# krajBB-Moj_i__MatejFIN2.net
KiCad netlist of a schematic drawn in EAGLE
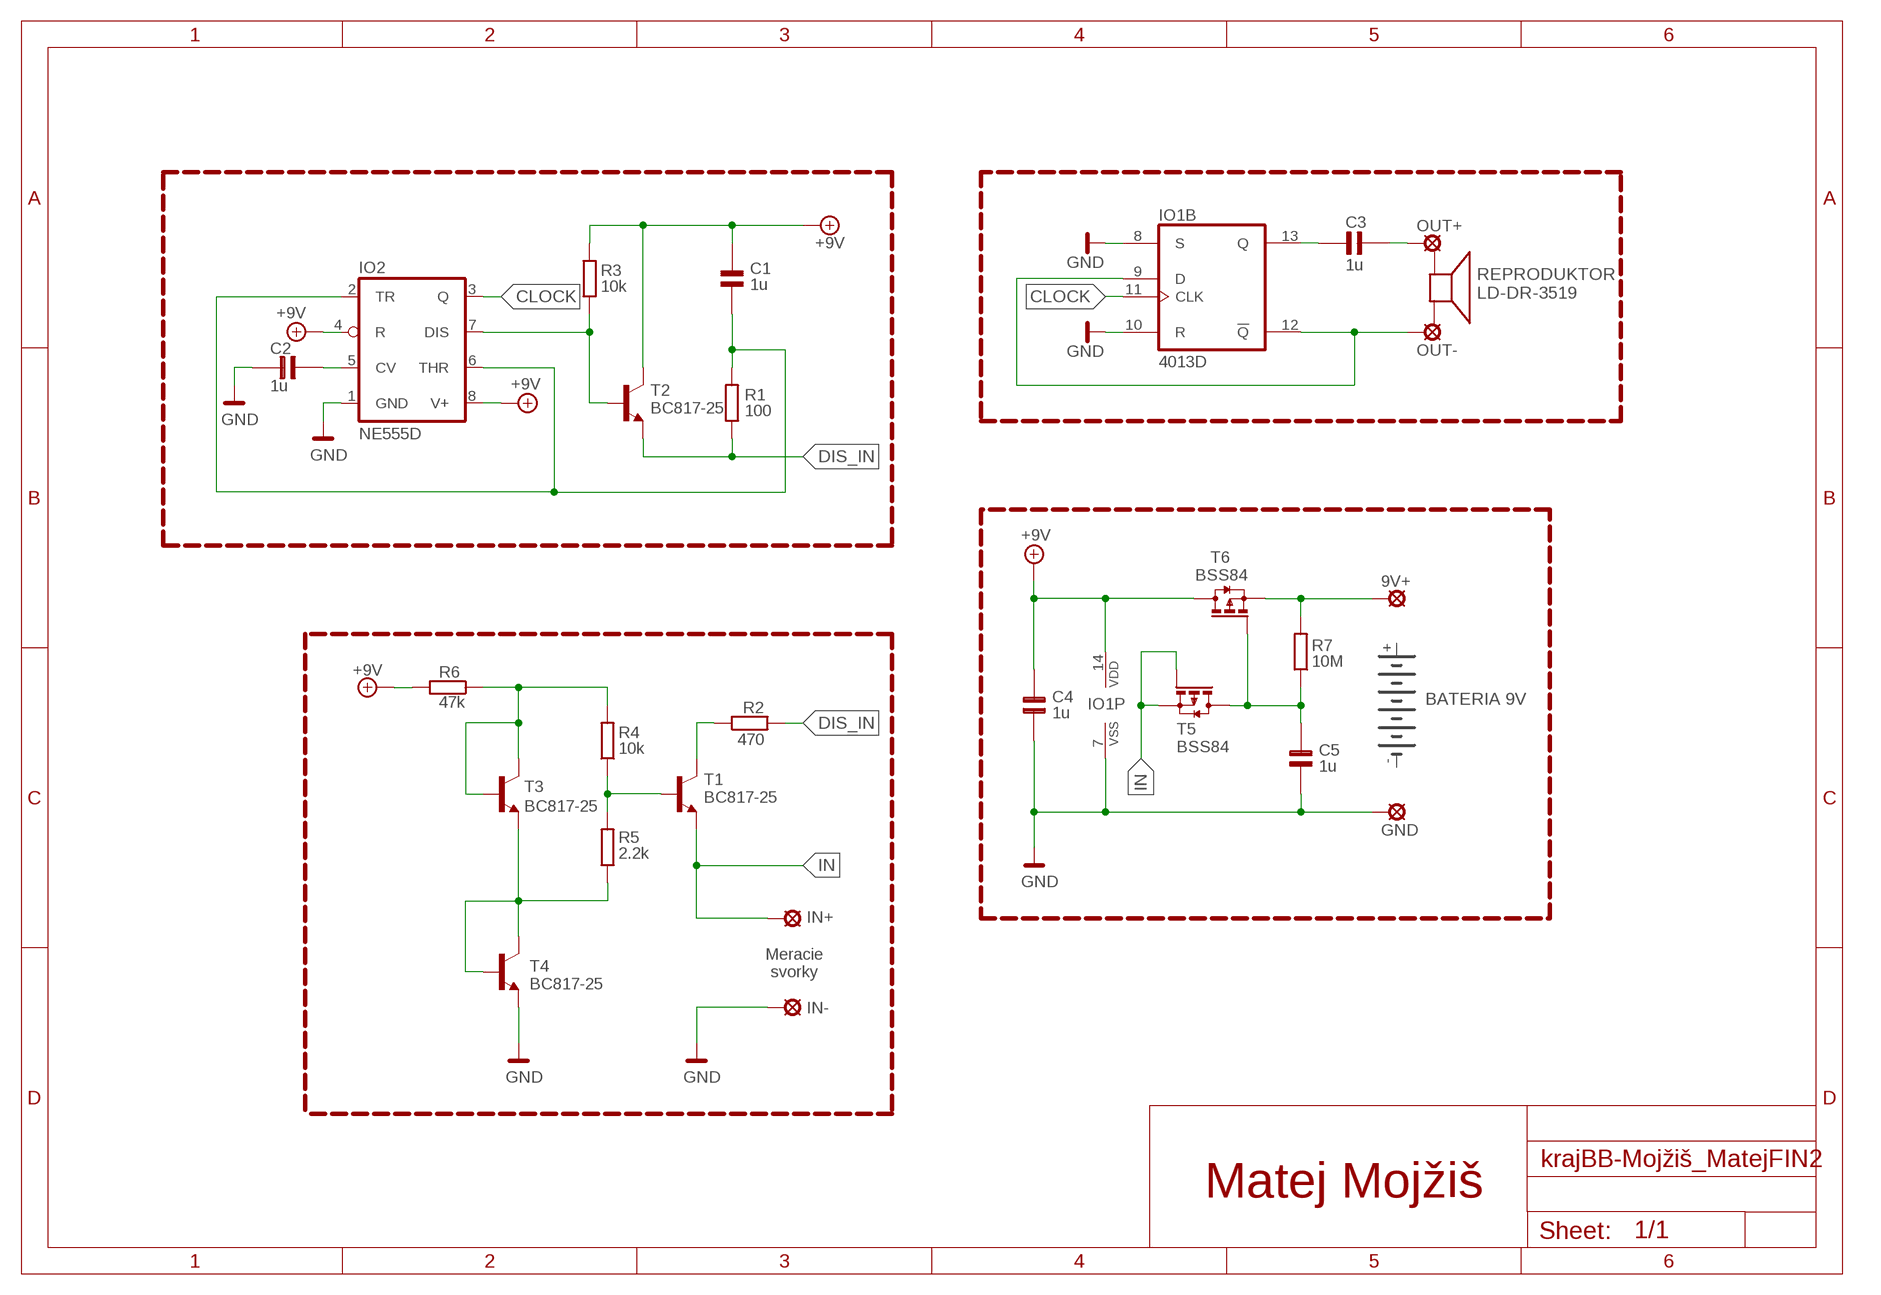
[diagram p0: schematic, sheet 1]

(export (version "E")
  (design (tool "Eeschema 10.0.6"))
  (components
    (comp (ref "9V+")
      (value "SMD3X3")
      (footprint "eagle-import:SMD3X3")
      (libsource (lib "eagle-import") (part "SMD3X3"))
    )
    (comp (ref "C1")
      (value "1u")
      (footprint "eagle-import:1206")
      (libsource (lib "eagle-import") (part "C1206TOP"))
    )
    (comp (ref "C2")
      (value "1u")
      (footprint "eagle-import:1206")
      (libsource (lib "eagle-import") (part "C1206TOP"))
    )
    (comp (ref "C3")
      (value "1u")
      (footprint "eagle-import:1206")
      (libsource (lib "eagle-import") (part "C1206TOP"))
    )
    (comp (ref "C4")
      (value "1u")
      (footprint "eagle-import:1206")
      (libsource (lib "eagle-import") (part "C1206TOP"))
    )
    (comp (ref "C5")
      (value "1u")
      (footprint "eagle-import:1206")
      (libsource (lib "eagle-import") (part "C1206TOP"))
    )
    (comp (ref "GND")
      (value "SMD3X3")
      (footprint "eagle-import:SMD3X3")
      (libsource (lib "eagle-import") (part "SMD3X3"))
    )
    (comp (ref "IN+")
      (value "SMD3X3")
      (footprint "eagle-import:SMD3X3")
      (libsource (lib "eagle-import") (part "SMD3X3"))
    )
    (comp (ref "IN-")
      (value "SMD3X3")
      (footprint "eagle-import:SMD3X3")
      (libsource (lib "eagle-import") (part "SMD3X3"))
    )
    (comp (ref "IO1")
      (value "4013D")
      (footprint "eagle-import:SO14")
      (libsource (lib "eagle-import") (part "4013D"))
    )
    (comp (ref "IO2")
      (value "NE555D")
      (footprint "eagle-import:SO08")
      (libsource (lib "eagle-import") (part "555DNE"))
    )
    (comp (ref "OUT+")
      (value "SMD3X3")
      (footprint "eagle-import:SMD3X3")
      (libsource (lib "eagle-import") (part "SMD3X3"))
    )
    (comp (ref "OUT-")
      (value "SMD3X3")
      (footprint "eagle-import:SMD3X3")
      (libsource (lib "eagle-import") (part "SMD3X3"))
    )
    (comp (ref "R1")
      (value "100")
      (footprint "eagle-import:1206")
      (libsource (lib "eagle-import") (part "R1206TOP"))
    )
    (comp (ref "R2")
      (value "470")
      (footprint "eagle-import:1206")
      (libsource (lib "eagle-import") (part "R1206TOP"))
    )
    (comp (ref "R3")
      (value "10k")
      (footprint "eagle-import:1206")
      (libsource (lib "eagle-import") (part "R1206TOP"))
    )
    (comp (ref "R4")
      (value "10k")
      (footprint "eagle-import:1206")
      (libsource (lib "eagle-import") (part "R1206TOP"))
    )
    (comp (ref "R5")
      (value "2.2k")
      (footprint "eagle-import:1206")
      (libsource (lib "eagle-import") (part "R1206TOP"))
    )
    (comp (ref "R6")
      (value "47k")
      (footprint "eagle-import:1206")
      (libsource (lib "eagle-import") (part "R1206TOP"))
    )
    (comp (ref "R7")
      (value "10M")
      (footprint "eagle-import:1206")
      (libsource (lib "eagle-import") (part "R1206TOP"))
    )
    (comp (ref "REPRODUKTOR")
      (value "LD-DR-3519")
      (footprint "eagle-import:LD-DR-3519")
      (libsource (lib "eagle-import") (part "LD-DR-3519"))
    )
    (comp (ref "T1")
      (value "BC817-25")
      (footprint "eagle-import:SOT23-BEC")
      (libsource (lib "eagle-import") (part "BC817SMD-25"))
    )
    (comp (ref "T2")
      (value "BC817-25")
      (footprint "eagle-import:SOT23-BEC")
      (libsource (lib "eagle-import") (part "BC817SMD-25"))
    )
    (comp (ref "T3")
      (value "BC817-25")
      (footprint "eagle-import:SOT23-BEC")
      (libsource (lib "eagle-import") (part "BC817SMD-25"))
    )
    (comp (ref "T4")
      (value "BC817-25")
      (footprint "eagle-import:SOT23-BEC")
      (libsource (lib "eagle-import") (part "BC817SMD-25"))
    )
    (comp (ref "T5")
      (value "BSS84")
      (footprint "eagle-import:SOT23")
      (libsource (lib "eagle-import") (part "BSS84"))
    )
    (comp (ref "T6")
      (value "BSS84")
      (footprint "eagle-import:SOT23")
      (libsource (lib "eagle-import") (part "BSS84"))
    )
    (comp (ref "U$1")
      (value "9VBATTERY")
      (footprint "eagle-import:9VBATTERY")
      (libsource (lib "eagle-import") (part "9VBATTERY"))
    )
  )
  (nets
    (net (code "1") (name "+9V") (class "Default")
      (node (ref "C1") (pin "2") (pinfunction "2_2") (pintype "passive"))
      (node (ref "C4") (pin "2") (pinfunction "2_2") (pintype "passive"))
      (node (ref "IO1") (pin "14") (pinfunction "VDD_14") (pintype "power_in"))
      (node (ref "IO2") (pin "4") (pinfunction "R_4") (pintype "input"))
      (node (ref "IO2") (pin "8") (pinfunction "V+_8") (pintype "power_in"))
      (node (ref "R3") (pin "2") (pinfunction "2_2") (pintype "passive"))
      (node (ref "R6") (pin "2") (pinfunction "2_2") (pintype "passive"))
      (node (ref "T2") (pin "C") (pinfunction "C_C") (pintype "passive"))
      (node (ref "T6") (pin "3") (pinfunction "D_3") (pintype "passive"))
    )
    (net (code "2") (name "CLOCK") (class "Default")
      (node (ref "IO1") (pin "11") (pinfunction "CLK_11") (pintype "input"))
      (node (ref "IO2") (pin "3") (pinfunction "Q_3") (pintype "output"))
    )
    (net (code "3") (name "DIS_IN") (class "Default")
      (node (ref "R1") (pin "1") (pinfunction "1_1") (pintype "passive"))
      (node (ref "R2") (pin "2") (pinfunction "2_2") (pintype "passive"))
      (node (ref "T2") (pin "E") (pinfunction "E_E") (pintype "passive"))
    )
    (net (code "4") (name "GND") (class "Default")
      (node (ref "C2") (pin "1") (pinfunction "1_1") (pintype "passive"))
      (node (ref "C4") (pin "1") (pinfunction "1_1") (pintype "passive"))
      (node (ref "C5") (pin "1") (pinfunction "1_1") (pintype "passive"))
      (node (ref "GND") (pin "P$1") (pinfunction "MP_P$1") (pintype "passive"))
      (node (ref "IN-") (pin "P$1") (pinfunction "MP_P$1") (pintype "passive"))
      (node (ref "IO1") (pin "10") (pinfunction "R_10") (pintype "input"))
      (node (ref "IO1") (pin "7") (pinfunction "VSS_7") (pintype "power_in"))
      (node (ref "IO1") (pin "8") (pinfunction "S_8") (pintype "input"))
      (node (ref "IO2") (pin "1") (pinfunction "GND_1") (pintype "power_in"))
      (node (ref "T4") (pin "E") (pinfunction "E_E") (pintype "passive"))
    )
    (net (code "5") (name "IN") (class "Default")
      (node (ref "IN+") (pin "P$1") (pinfunction "MP_P$1") (pintype "passive"))
      (node (ref "T1") (pin "E") (pinfunction "E_E") (pintype "passive"))
      (node (ref "T5") (pin "1") (pinfunction "G_1") (pintype "passive"))
      (node (ref "T5") (pin "2") (pinfunction "S_2") (pintype "passive"))
    )
    (net (code "6") (name "Net-(9V+-MP)") (class "Default")
      (node (ref "9V+") (pin "P$1") (pinfunction "MP_P$1") (pintype "passive"))
      (node (ref "R7") (pin "2") (pinfunction "2_2") (pintype "passive"))
      (node (ref "T6") (pin "2") (pinfunction "S_2") (pintype "passive"))
    )
    (net (code "7") (name "Net-(IO1B-D)") (class "Default")
      (node (ref "IO1") (pin "12") (pinfunction "~{Q}_12") (pintype "output"))
      (node (ref "IO1") (pin "9") (pinfunction "D_9") (pintype "input"))
      (node (ref "OUT-") (pin "P$1") (pinfunction "MP_P$1") (pintype "passive"))
    )
    (net (code "8") (name "Net-(IO1B-Q)") (class "Default")
      (node (ref "C3") (pin "1") (pinfunction "1_1") (pintype "passive"))
      (node (ref "IO1") (pin "13") (pinfunction "Q_13") (pintype "output"))
    )
    (net (code "9") (name "Net-(IO2-CV)") (class "Default")
      (node (ref "C2") (pin "2") (pinfunction "2_2") (pintype "passive"))
      (node (ref "IO2") (pin "5") (pinfunction "CV_5") (pintype "input"))
    )
    (net (code "10") (name "Net-(IO2-DIS)") (class "Default")
      (node (ref "IO2") (pin "7") (pinfunction "DIS_7") (pintype "input"))
      (node (ref "R3") (pin "1") (pinfunction "1_1") (pintype "passive"))
      (node (ref "T2") (pin "B") (pinfunction "B_B") (pintype "passive"))
    )
    (net (code "11") (name "Net-(IO2-THR)") (class "Default")
      (node (ref "C1") (pin "1") (pinfunction "1_1") (pintype "passive"))
      (node (ref "IO2") (pin "2") (pinfunction "TR_2") (pintype "input"))
      (node (ref "IO2") (pin "6") (pinfunction "THR_6") (pintype "input"))
      (node (ref "R1") (pin "2") (pinfunction "2_2") (pintype "passive"))
    )
    (net (code "12") (name "Net-(OUT+-MP)") (class "Default")
      (node (ref "C3") (pin "2") (pinfunction "2_2") (pintype "passive"))
      (node (ref "OUT+") (pin "P$1") (pinfunction "MP_P$1") (pintype "passive"))
    )
    (net (code "13") (name "Net-(R2-Pad1)") (class "Default")
      (node (ref "R2") (pin "1") (pinfunction "1_1") (pintype "passive"))
      (node (ref "T1") (pin "C") (pinfunction "C_C") (pintype "passive"))
    )
    (net (code "14") (name "Net-(R4-Pad1)") (class "Default")
      (node (ref "R4") (pin "1") (pinfunction "1_1") (pintype "passive"))
      (node (ref "R5") (pin "2") (pinfunction "2_2") (pintype "passive"))
      (node (ref "T1") (pin "B") (pinfunction "B_B") (pintype "passive"))
    )
    (net (code "15") (name "Net-(R4-Pad2)") (class "Default")
      (node (ref "R4") (pin "2") (pinfunction "2_2") (pintype "passive"))
      (node (ref "R6") (pin "1") (pinfunction "1_1") (pintype "passive"))
      (node (ref "T3") (pin "B") (pinfunction "B_B") (pintype "passive"))
      (node (ref "T3") (pin "C") (pinfunction "C_C") (pintype "passive"))
    )
    (net (code "16") (name "Net-(R5-Pad1)") (class "Default")
      (node (ref "R5") (pin "1") (pinfunction "1_1") (pintype "passive"))
      (node (ref "T3") (pin "E") (pinfunction "E_E") (pintype "passive"))
      (node (ref "T4") (pin "B") (pinfunction "B_B") (pintype "passive"))
      (node (ref "T4") (pin "C") (pinfunction "C_C") (pintype "passive"))
    )
    (net (code "17") (name "Net-(T5-D)") (class "Default")
      (node (ref "C5") (pin "2") (pinfunction "2_2") (pintype "passive"))
      (node (ref "R7") (pin "1") (pinfunction "1_1") (pintype "passive"))
      (node (ref "T5") (pin "3") (pinfunction "D_3") (pintype "passive"))
      (node (ref "T6") (pin "1") (pinfunction "G_1") (pintype "passive"))
    )
    (net (code "18") (name "unconnected-(REPRODUKTOR-1-PadP$1)") (class "Default")
      (node (ref "REPRODUKTOR") (pin "P$1") (pinfunction "1_P$1") (pintype "passive"))
    )
    (net (code "19") (name "unconnected-(REPRODUKTOR-2-PadP$2)") (class "Default")
      (node (ref "REPRODUKTOR") (pin "P$2") (pinfunction "2_P$2") (pintype "passive"))
    )
  )
)
